# MCU.net
KiCad netlist of a schematic drawn in Altium Designer
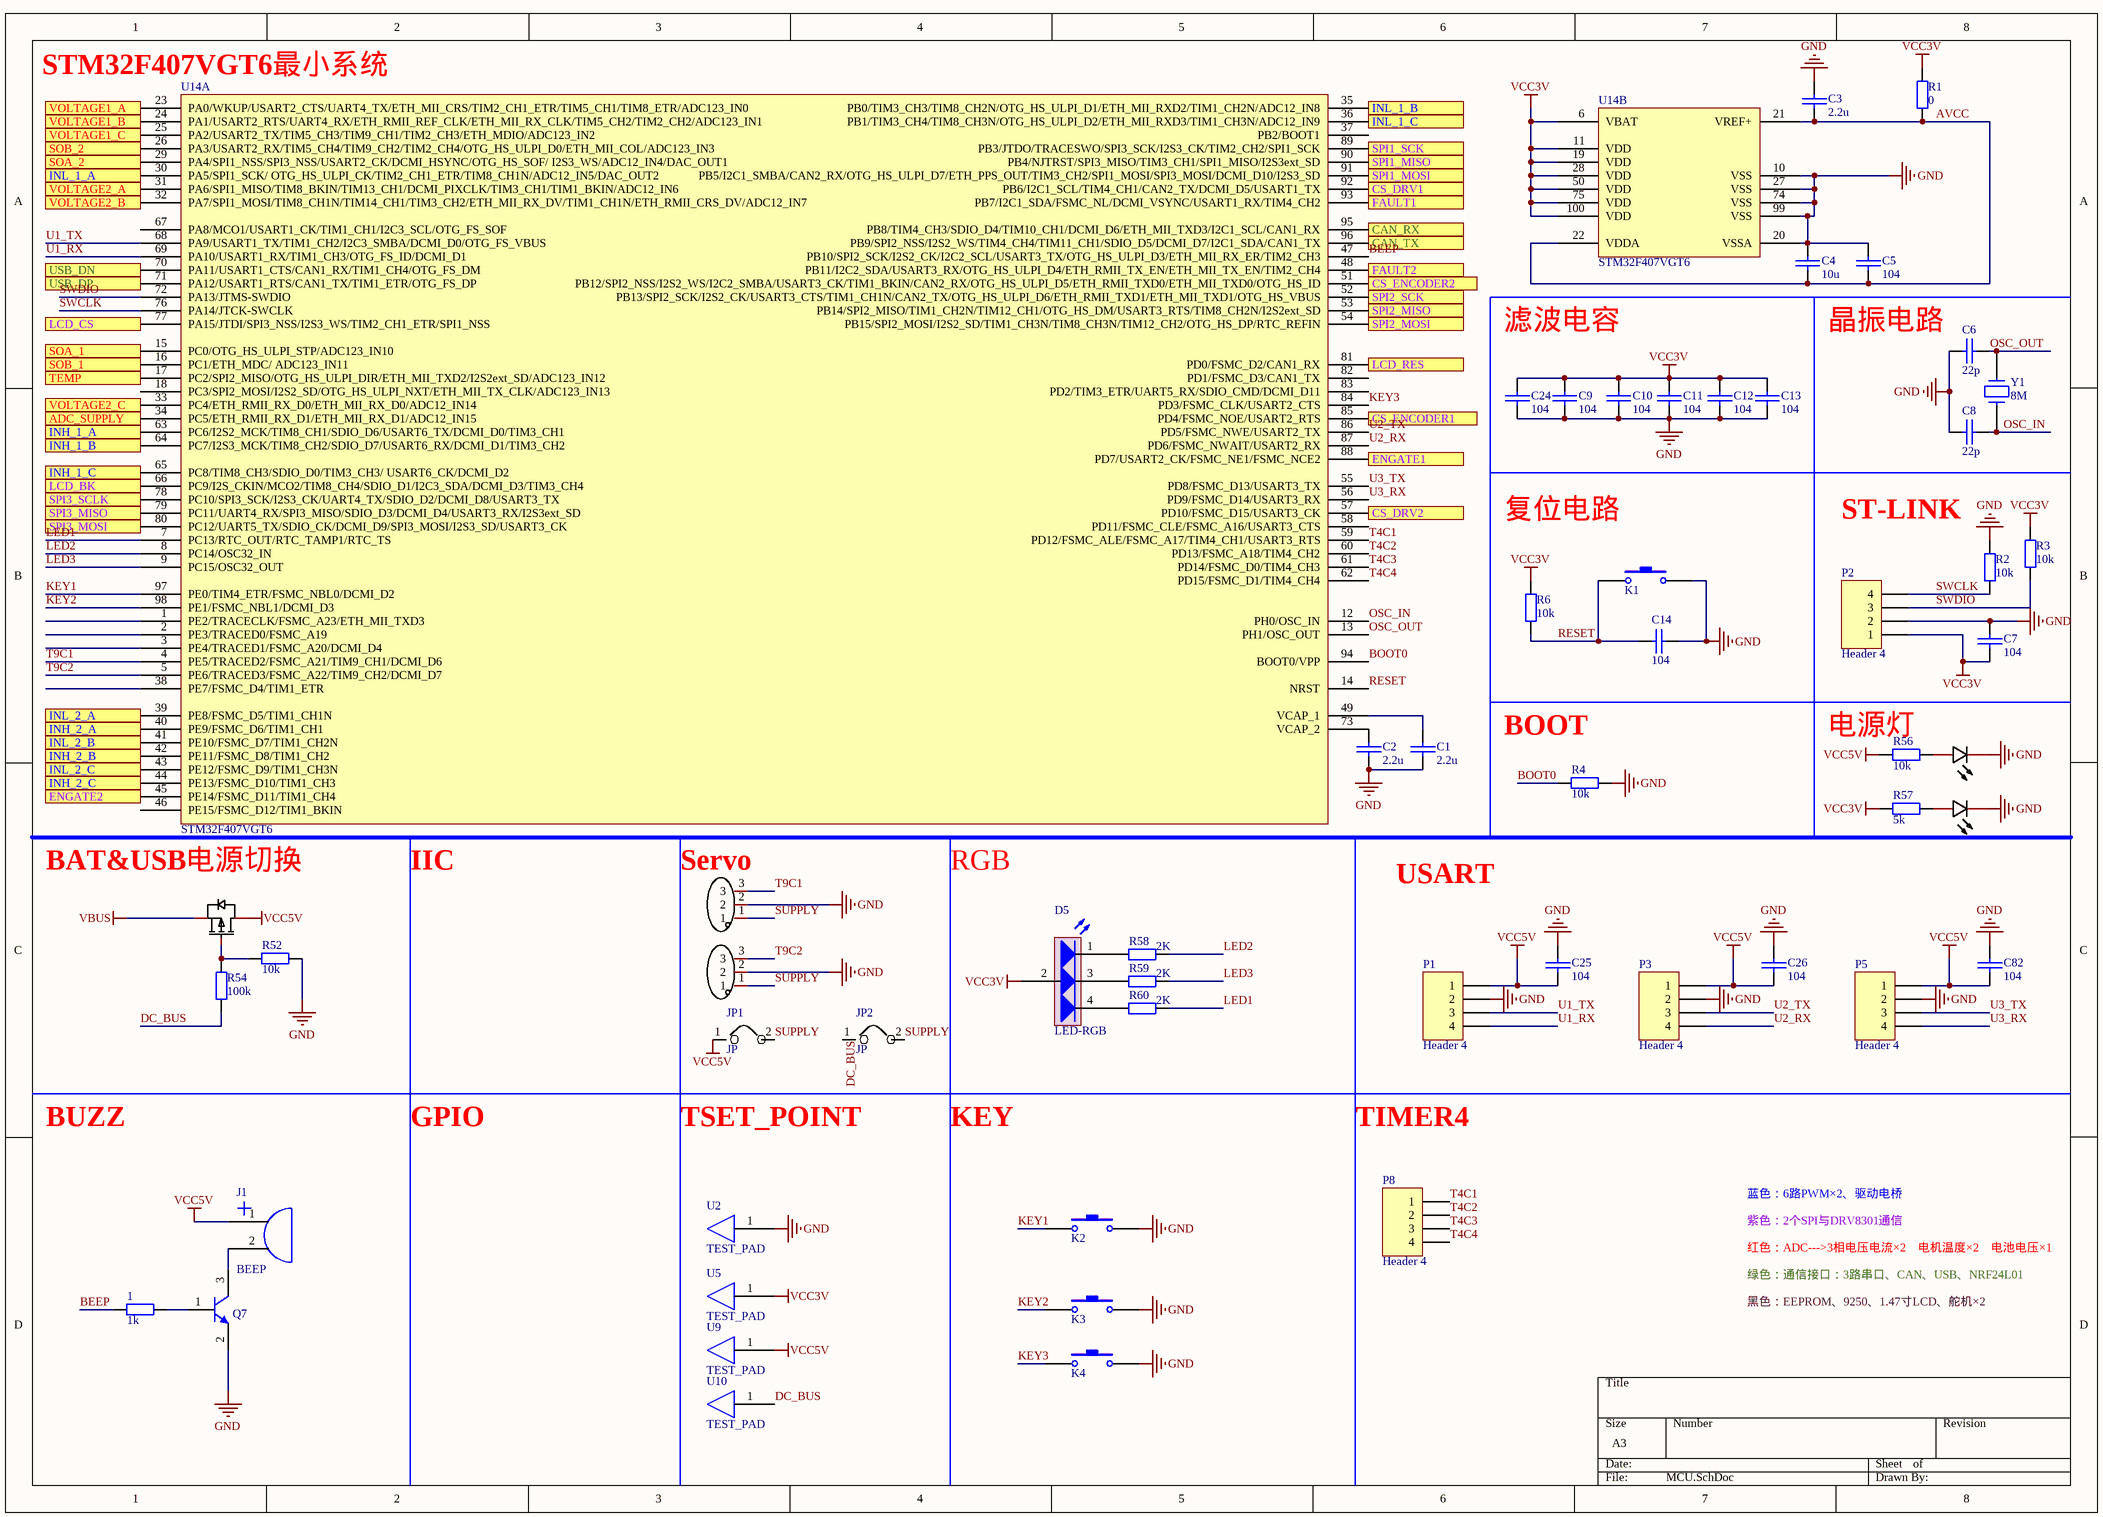
[diagram p0: MCU.SchDoc]

(export (version "E")
  (design (tool "Eeschema 10.0.6"))
  (components
    (comp (ref "1")
      (value "1k")
      (footprint "0402C")
      (description "Resistor")
      (fields (field (name "PUBLISHER") "Altium Limited"))
      (libsource (lib "") (part "Res2_1"))
    )
    (comp (ref "2")
      (value "NCD0603R1_C84263")
      (footprint "0603LED")
      (fields (field (name "MANUFACTURER") "国星光电") (field (name "MANUFACTURER PART") "NCD0603R1"))
      (libsource (lib "FOC") (part "0603LED"))
    )
    (comp (ref "3")
      (value "NCD0603R1_C84263")
      (footprint "0603LED")
      (fields (field (name "MANUFACTURER") "国星光电") (field (name "MANUFACTURER PART") "NCD0603R1"))
      (libsource (lib "FOC") (part "0603LED"))
    )
    (comp (ref "C1")
      (value "2.2u")
      (footprint "0402C")
      (fields (field (name "Comment") "CAP"))
      (libsource (lib "MY SCH LIB") (part "CAP"))
    )
    (comp (ref "C2")
      (value "2.2u")
      (footprint "0402C")
      (fields (field (name "Comment") "CAP"))
      (libsource (lib "MY SCH LIB") (part "CAP"))
    )
    (comp (ref "C3")
      (value "2.2u")
      (footprint "0402C")
      (fields (field (name "Comment") "CAP"))
      (libsource (lib "MY SCH LIB") (part "CAP"))
    )
    (comp (ref "C4")
      (value "10u")
      (footprint "0402C")
      (fields (field (name "Comment") "CAP"))
      (libsource (lib "MY SCH LIB") (part "CAP"))
    )
    (comp (ref "C5")
      (value "104")
      (footprint "0402C")
      (fields (field (name "Comment") "CAP"))
      (libsource (lib "MY SCH LIB") (part "CAP"))
    )
    (comp (ref "C6")
      (value "22p")
      (footprint "0402C")
      (fields (field (name "Comment") "CAP"))
      (libsource (lib "MY SCH LIB") (part "CAP"))
    )
    (comp (ref "C7")
      (value "104")
      (footprint "0402C")
      (fields (field (name "Comment") "CAP"))
      (libsource (lib "MY SCH LIB") (part "CAP"))
    )
    (comp (ref "C8")
      (value "22p")
      (footprint "0402C")
      (fields (field (name "Comment") "CAP"))
      (libsource (lib "MY SCH LIB") (part "CAP"))
    )
    (comp (ref "C9")
      (value "104")
      (footprint "0402C")
      (fields (field (name "Comment") "CAP"))
      (libsource (lib "MY SCH LIB") (part "CAP"))
    )
    (comp (ref "C10")
      (value "104")
      (footprint "0402C")
      (fields (field (name "Comment") "CAP"))
      (libsource (lib "MY SCH LIB") (part "CAP"))
    )
    (comp (ref "C11")
      (value "104")
      (footprint "0402C")
      (fields (field (name "Comment") "CAP"))
      (libsource (lib "MY SCH LIB") (part "CAP"))
    )
    (comp (ref "C12")
      (value "104")
      (footprint "0402C")
      (fields (field (name "Comment") "CAP"))
      (libsource (lib "MY SCH LIB") (part "CAP"))
    )
    (comp (ref "C13")
      (value "104")
      (footprint "0402C")
      (fields (field (name "Comment") "CAP"))
      (libsource (lib "MY SCH LIB") (part "CAP"))
    )
    (comp (ref "C14") (value "104") (footprint "0402C") (libsource (lib "平衡车") (part "CAP")))
    (comp (ref "C24")
      (value "104")
      (footprint "0402C")
      (fields (field (name "Comment") "CAP"))
      (libsource (lib "MY SCH LIB") (part "CAP"))
    )
    (comp (ref "C25")
      (value "104")
      (footprint "0402C")
      (description "Capacitor")
      (libsource (lib "Y常用") (part "Cap"))
    )
    (comp (ref "C26")
      (value "104")
      (footprint "0402C")
      (description "Capacitor")
      (libsource (lib "Y常用") (part "Cap"))
    )
    (comp (ref "C82")
      (value "104")
      (footprint "0402C")
      (description "Capacitor")
      (libsource (lib "Y常用") (part "Cap"))
    )
    (comp (ref "D5")
      (value "LED-RGB")
      (footprint "RGB")
      (description "三基色LED")
      (fields (field (name "PUBLISHER") "Altium Limited"))
      (libsource (lib "SMC_Devices") (part "LED-RGB"))
    )
    (comp (ref "J1")
      (value "BEEP")
      (footprint "无源蜂鸣器5020")
      (description "蜂鸣器")
      (libsource (lib "MY SCH LIB") (part "BEEP"))
    )
    (comp (ref "JP1") (value "JP") (footprint "跳线") (libsource (lib "FOC") (part "JP")))
    (comp (ref "JP2") (value "JP") (footprint "跳线") (libsource (lib "FOC") (part "JP")))
    (comp (ref "K1")
      (value "KEY")
      (footprint "KEY-SMD_L3.9-W3.0-P4.45")
      (libsource (lib "FOC") (part "KEY_1"))
    )
    (comp (ref "K2")
      (value "KEY")
      (footprint "KEY-SMD_L3.9-W3.0-P4.45")
      (libsource (lib "FOC") (part "KEY_1"))
    )
    (comp (ref "K3")
      (value "KEY")
      (footprint "KEY-SMD_L3.9-W3.0-P4.45")
      (libsource (lib "FOC") (part "KEY_1"))
    )
    (comp (ref "K4")
      (value "KEY")
      (footprint "KEY-SMD_L3.9-W3.0-P4.45")
      (libsource (lib "FOC") (part "KEY_1"))
    )
    (comp (ref "P1")
      (value "Header 4")
      (footprint "A1002WR-S-4P")
      (description "Header, 4-Pin")
      (fields (field (name "PUBLISHER") "Altium Limited"))
      (libsource (lib "FOC") (part "Header 4"))
    )
    (comp (ref "P2")
      (value "Header 4")
      (footprint "A1002WR-S-4P")
      (description "Header, 4-Pin")
      (fields (field (name "PUBLISHER") "Altium Limited"))
      (libsource (lib "MY SCH LIB__JCH") (part "Header 4"))
    )
    (comp (ref "P3")
      (value "Header 4")
      (footprint "A1002WR-S-4P")
      (description "Header, 4-Pin")
      (fields (field (name "PUBLISHER") "Altium Limited"))
      (libsource (lib "FOC") (part "Header 4"))
    )
    (comp (ref "P5")
      (value "Header 4")
      (footprint "A1002WR-S-4P")
      (description "Header, 4-Pin")
      (fields (field (name "PUBLISHER") "Altium Limited"))
      (libsource (lib "FOC") (part "Header 4"))
    )
    (comp (ref "P8")
      (value "Header 4")
      (footprint "A1002WR-S-4P")
      (description "Header, 4-Pin")
      (fields (field (name "PUBLISHER") "Altium Limited"))
      (libsource (lib "FOC") (part "Header 4"))
    )
    (comp (ref "Q7") (value "NPN") (footprint "SOT-23Q") (libsource (lib "MY SCH LIB__JCH") (part "NPN")))
    (comp (ref "Q15")
      (value "AO3401_C727156")
      (footprint "SOT-23Q")
      (fields (field (name "MANUFACTURER") "TWGMC(台湾迪嘉)") (field (name "MANUFACTURER PART") "AO3401"))
      (libsource (lib "FOC") (part "PMOS"))
    )
    (comp (ref "R1")
      (value "0")
      (footprint "0402R")
      (description "Resistor")
      (fields (field (name "PUBLISHER") "Altium Limited"))
      (libsource (lib "") (part "Res2_2"))
    )
    (comp (ref "R2")
      (value "10k")
      (footprint "0402R")
      (description "Resistor")
      (fields (field (name "PUBLISHER") "Altium Limited"))
      (libsource (lib "Miscellaneous Devices") (part "Res2"))
    )
    (comp (ref "R3")
      (value "10k")
      (footprint "0402R")
      (description "Resistor")
      (fields (field (name "PUBLISHER") "Altium Limited"))
      (libsource (lib "Miscellaneous Devices") (part "Res2"))
    )
    (comp (ref "R4")
      (value "10k")
      (footprint "0402R")
      (description "Resistor")
      (fields (field (name "PUBLISHER") "Altium Limited"))
      (libsource (lib "") (part "Res2_1"))
    )
    (comp (ref "R6")
      (value "10k")
      (footprint "0402R")
      (description "Resistor")
      (fields (field (name "PUBLISHER") "Altium Limited"))
      (libsource (lib "") (part "Res2_2"))
    )
    (comp (ref "R52")
      (value "10k")
      (footprint "0402R")
      (description "Resistor")
      (fields (field (name "PUBLISHER") "Altium Limited"))
      (libsource (lib "") (part "Res2_3"))
    )
    (comp (ref "R54")
      (value "100k")
      (footprint "0402R")
      (description "Resistor")
      (fields (field (name "PUBLISHER") "Altium Limited"))
      (libsource (lib "") (part "Res2_2"))
    )
    (comp (ref "R56")
      (value "10k")
      (footprint "0402R")
      (description "Resistor")
      (fields (field (name "PUBLISHER") "Altium Limited"))
      (libsource (lib "") (part "Res2_1"))
    )
    (comp (ref "R57")
      (value "5k")
      (footprint "0402R")
      (description "Resistor")
      (fields (field (name "PUBLISHER") "Altium Limited"))
      (libsource (lib "") (part "Res2_1"))
    )
    (comp (ref "R58")
      (value "2K")
      (footprint "0402R")
      (description "贴片电阻")
      (fields (field (name "Comment") "Res1") (field (name "PUBLISHER") "Altium Limited"))
      (libsource (lib "SMC_Devices") (part "Res1"))
    )
    (comp (ref "R59")
      (value "2K")
      (footprint "0402R")
      (description "贴片电阻")
      (fields (field (name "Comment") "Res1") (field (name "PUBLISHER") "Altium Limited"))
      (libsource (lib "SMC_Devices") (part "Res1"))
    )
    (comp (ref "R60")
      (value "2K")
      (footprint "0402R")
      (description "贴片电阻")
      (fields (field (name "Comment") "Res1") (field (name "PUBLISHER") "Altium Limited"))
      (libsource (lib "SMC_Devices") (part "Res1"))
    )
    (comp (ref "U2")
      (value "TEST_PAD")
      (footprint "TEST_PAD -SQUARE")
      (libsource (lib "FOC") (part "TEST_PAD"))
    )
    (comp (ref "U3")
      (value "MR30-M")
      (footprint "HDR2.54-LI-3P")
      (fields (field (name "MANUFACTURER") "AMASS(艾迈斯)"))
      (libsource (lib "FOC") (part "MR30-M"))
    )
    (comp (ref "U4")
      (value "MR30-M")
      (footprint "HDR2.54-LI-3P")
      (fields (field (name "MANUFACTURER") "AMASS(艾迈斯)"))
      (libsource (lib "FOC") (part "MR30-M"))
    )
    (comp (ref "U5")
      (value "TEST_PAD")
      (footprint "TEST_PAD -SQUARE")
      (libsource (lib "FOC") (part "TEST_PAD"))
    )
    (comp (ref "U9")
      (value "TEST_PAD")
      (footprint "TEST_PAD -SQUARE")
      (libsource (lib "FOC") (part "TEST_PAD"))
    )
    (comp (ref "U10")
      (value "TEST_PAD")
      (footprint "TEST_PAD -SQUARE")
      (libsource (lib "FOC") (part "TEST_PAD"))
    )
    (comp (ref "U14")
      (value "STM32F407VGT6")
      (footprint "LQFP-100_L14.0-W14.0-P0.50-LS16.0-BL")
      (libsource (lib "FOC") (part "STM32F407VGT6"))
    )
    (comp (ref "Y1")
      (value "8M")
      (footprint "晶振")
      (description "Crystal")
      (libsource (lib "MY SCH LIB") (part "CRYSTAL"))
    )
  )
  (nets
    (net (code "1") (name "/ADC_SUPPLY") (class "Default")
      (node (ref "U14") (pin "34") (pinfunction "PC5/ETH_RMII_RX_D1/ETH_MII_RX_D1/ADC12_IN15_34") (pintype "passive"))
    )
    (net (code "2") (name "/AVCC") (class "Default")
      (node (ref "C3") (pin "1") (pinfunction "1_1") (pintype "passive"))
      (node (ref "C4") (pin "2") (pinfunction "2_2") (pintype "passive"))
      (node (ref "C5") (pin "2") (pinfunction "2_2") (pintype "passive"))
      (node (ref "R1") (pin "2") (pinfunction "2_2") (pintype "passive"))
      (node (ref "U14") (pin "21") (pinfunction "VREF+_21") (pintype "passive"))
      (node (ref "U14") (pin "22") (pinfunction "VDDA_22") (pintype "passive"))
    )
    (net (code "3") (name "/BEEP") (class "Default")
      (node (ref "1") (pin "1") (pinfunction "1_1") (pintype "passive"))
      (node (ref "U14") (pin "47") (pinfunction "PB10/SPI2_SCK/I2S2_CK/I2C2_SCL/USART3_TX/OTG_HS_ULPI_D3/ETH_MII_RX_ER/TIM2_CH3_47") (pintype "passive"))
    )
    (net (code "4") (name "/BOOT0") (class "Default")
      (node (ref "R4") (pin "1") (pinfunction "1_1") (pintype "passive"))
      (node (ref "U14") (pin "94") (pinfunction "BOOT0/VPP_94") (pintype "passive"))
    )
    (net (code "5") (name "/CAN_RX") (class "Default")
      (node (ref "U14") (pin "95") (pinfunction "PB8/TIM4_CH3/SDIO_D4/TIM10_CH1/DCMI_D6/ETH_MII_TXD3/I2C1_SCL/CAN1_RX_95") (pintype "passive"))
    )
    (net (code "6") (name "/CAN_TX") (class "Default")
      (node (ref "U14") (pin "96") (pinfunction "PB9/SPI2_NSS/I2S2_WS/TIM4_CH4/TIM11_CH1/SDIO_D5/DCMI_D7/I2C1_SDA/CAN1_TX_96") (pintype "passive"))
    )
    (net (code "7") (name "/CS_DRV1") (class "Default")
      (node (ref "U14") (pin "92") (pinfunction "PB6/I2C1_SCL/TIM4_CH1/CAN2_TX/DCMI_D5/USART1_TX_92") (pintype "passive"))
    )
    (net (code "8") (name "/CS_DRV2") (class "Default")
      (node (ref "U14") (pin "57") (pinfunction "PD10/FSMC_D15/USART3_CK_57") (pintype "passive"))
    )
    (net (code "9") (name "/CS_ENCODER1") (class "Default")
      (node (ref "U14") (pin "85") (pinfunction "PD4/FSMC_NOE/USART2_RTS_85") (pintype "passive"))
    )
    (net (code "10") (name "/CS_ENCODER2") (class "Default")
      (node (ref "U14") (pin "51") (pinfunction "PB12/SPI2_NSS/I2S2_WS/I2C2_SMBA/USART3_CK/TIM1_BKIN/CAN2_RX/OTG_HS_ULPI_D5/ETH_RMII_TXD0/ETH_MII_TXD0/OTG_HS_ID_51") (pintype "passive"))
    )
    (net (code "11") (name "/DC_BUS") (class "Default")
      (node (ref "JP2") (pin "1") (pinfunction "1_1") (pintype "passive"))
      (node (ref "R54") (pin "2") (pinfunction "2_2") (pintype "passive"))
      (node (ref "U10") (pin "1") (pinfunction "2_1") (pintype "passive"))
    )
    (net (code "12") (name "/ENGATE1") (class "Default")
      (node (ref "U14") (pin "88") (pinfunction "PD7/USART2_CK/FSMC_NE1/FSMC_NCE2_88") (pintype "passive"))
    )
    (net (code "13") (name "/ENGATE2") (class "Default")
      (node (ref "U14") (pin "45") (pinfunction "PE14/FSMC_D11/TIM1_CH4_45") (pintype "passive"))
    )
    (net (code "14") (name "/FAULT1") (class "Default")
      (node (ref "U14") (pin "93") (pinfunction "PB7/I2C1_SDA/FSMC_NL/DCMI_VSYNC/USART1_RX/TIM4_CH2_93") (pintype "passive"))
    )
    (net (code "15") (name "/FAULT2") (class "Default")
      (node (ref "U14") (pin "48") (pinfunction "PB11/I2C2_SDA/USART3_RX/OTG_HS_ULPI_D4/ETH_RMII_TX_EN/ETH_MII_TX_EN/TIM2_CH4_48") (pintype "passive"))
    )
    (net (code "16") (name "/INH_1_A") (class "Default")
      (node (ref "U14") (pin "63") (pinfunction "PC6/I2S2_MCK/TIM8_CH1/SDIO_D6/USART6_TX/DCMI_D0/TIM3_CH1_63") (pintype "passive"))
    )
    (net (code "17") (name "/INH_1_B") (class "Default")
      (node (ref "U14") (pin "64") (pinfunction "PC7/I2S3_MCK/TIM8_CH2/SDIO_D7/USART6_RX/DCMI_D1/TIM3_CH2_64") (pintype "passive"))
    )
    (net (code "18") (name "/INH_1_C") (class "Default")
      (node (ref "U14") (pin "65") (pinfunction "PC8/TIM8_CH3/SDIO_D0/TIM3_CH3/_USART6_CK/DCMI_D2_65") (pintype "passive"))
    )
    (net (code "19") (name "/INH_2_A") (class "Default")
      (node (ref "U14") (pin "40") (pinfunction "PE9/FSMC_D6/TIM1_CH1_40") (pintype "passive"))
    )
    (net (code "20") (name "/INH_2_B") (class "Default")
      (node (ref "U14") (pin "42") (pinfunction "PE11/FSMC_D8/TIM1_CH2_42") (pintype "passive"))
    )
    (net (code "21") (name "/INH_2_C") (class "Default")
      (node (ref "U14") (pin "44") (pinfunction "PE13/FSMC_D10/TIM1_CH3_44") (pintype "passive"))
    )
    (net (code "22") (name "/INL_1_A") (class "Default")
      (node (ref "U14") (pin "30") (pinfunction "PA5/SPI1_SCK/_OTG_HS_ULPI_CK/TIM2_CH1_ETR/TIM8_CH1N/ADC12_IN5/DAC_OUT2_30") (pintype "passive"))
    )
    (net (code "23") (name "/INL_1_B") (class "Default")
      (node (ref "U14") (pin "35") (pinfunction "PB0/TIM3_CH3/TIM8_CH2N/OTG_HS_ULPI_D1/ETH_MII_RXD2/TIM1_CH2N/ADC12_IN8_35") (pintype "passive"))
    )
    (net (code "24") (name "/INL_1_C") (class "Default")
      (node (ref "U14") (pin "36") (pinfunction "PB1/TIM3_CH4/TIM8_CH3N/OTG_HS_ULPI_D2/ETH_MII_RXD3/TIM1_CH3N/ADC12_IN9_36") (pintype "passive"))
    )
    (net (code "25") (name "/INL_2_A") (class "Default")
      (node (ref "U14") (pin "39") (pinfunction "PE8/FSMC_D5/TIM1_CH1N_39") (pintype "passive"))
    )
    (net (code "26") (name "/INL_2_B") (class "Default")
      (node (ref "U14") (pin "41") (pinfunction "PE10/FSMC_D7/TIM1_CH2N_41") (pintype "passive"))
    )
    (net (code "27") (name "/INL_2_C") (class "Default")
      (node (ref "U14") (pin "43") (pinfunction "PE12/FSMC_D9/TIM1_CH3N_43") (pintype "passive"))
    )
    (net (code "28") (name "/KEY1") (class "Default")
      (node (ref "K2") (pin "1") (pinfunction "1_1") (pintype "passive"))
      (node (ref "U14") (pin "97") (pinfunction "PE0/TIM4_ETR/FSMC_NBL0/DCMI_D2_97") (pintype "passive"))
    )
    (net (code "29") (name "/KEY2") (class "Default")
      (node (ref "K3") (pin "1") (pinfunction "1_1") (pintype "passive"))
      (node (ref "U14") (pin "98") (pinfunction "PE1/FSMC_NBL1/DCMI_D3_98") (pintype "passive"))
    )
    (net (code "30") (name "/KEY3") (class "Default")
      (node (ref "K4") (pin "1") (pinfunction "1_1") (pintype "passive"))
      (node (ref "U14") (pin "84") (pinfunction "PD3/FSMC_CLK/USART2_CTS_84") (pintype "passive"))
    )
    (net (code "31") (name "/LCD_BK") (class "Default")
      (node (ref "U14") (pin "66") (pinfunction "PC9/I2S_CKIN/MCO2/TIM8_CH4/SDIO_D1/I2C3_SDA/DCMI_D3/TIM3_CH4_66") (pintype "passive"))
    )
    (net (code "32") (name "/LCD_CS") (class "Default")
      (node (ref "U14") (pin "77") (pinfunction "PA15/JTDI/SPI3_NSS/I2S3_WS/TIM2_CH1_ETR/SPI1_NSS_77") (pintype "passive"))
    )
    (net (code "33") (name "/LCD_RES") (class "Default")
      (node (ref "U14") (pin "81") (pinfunction "PD0/FSMC_D2/CAN1_RX_81") (pintype "passive"))
    )
    (net (code "34") (name "/LED1") (class "Default")
      (node (ref "R60") (pin "2") (pinfunction "2_2") (pintype "passive"))
      (node (ref "U14") (pin "7") (pinfunction "PC13/RTC_OUT/RTC_TAMP1/RTC_TS_7") (pintype "passive"))
    )
    (net (code "35") (name "/LED2") (class "Default")
      (node (ref "R58") (pin "2") (pinfunction "2_2") (pintype "passive"))
      (node (ref "U14") (pin "8") (pinfunction "PC14/OSC32_IN_8") (pintype "passive"))
    )
    (net (code "36") (name "/LED3") (class "Default")
      (node (ref "R59") (pin "2") (pinfunction "2_2") (pintype "passive"))
      (node (ref "U14") (pin "9") (pinfunction "PC15/OSC32_OUT_9") (pintype "passive"))
    )
    (net (code "37") (name "/OSC_IN") (class "Default")
      (node (ref "C8") (pin "1") (pinfunction "1_1") (pintype "passive"))
      (node (ref "U14") (pin "12") (pinfunction "PH0/OSC_IN_12") (pintype "passive"))
      (node (ref "Y1") (pin "2") (pinfunction "2_2") (pintype "passive"))
    )
    (net (code "38") (name "/OSC_OUT") (class "Default")
      (node (ref "C6") (pin "1") (pinfunction "1_1") (pintype "passive"))
      (node (ref "U14") (pin "13") (pinfunction "PH1/OSC_OUT_13") (pintype "passive"))
      (node (ref "Y1") (pin "1") (pinfunction "1_1") (pintype "passive"))
    )
    (net (code "39") (name "/RESET") (class "Default")
      (node (ref "C14") (pin "1") (pinfunction "1_1") (pintype "passive"))
      (node (ref "K1") (pin "1") (pinfunction "1_1") (pintype "passive"))
      (node (ref "R6") (pin "2") (pinfunction "2_2") (pintype "passive"))
      (node (ref "U14") (pin "14") (pinfunction "NRST_14") (pintype "passive"))
    )
    (net (code "40") (name "/SOA_1") (class "Default")
      (node (ref "U14") (pin "15") (pinfunction "PC0/OTG_HS_ULPI_STP/ADC123_IN10_15") (pintype "passive"))
    )
    (net (code "41") (name "/SOA_2") (class "Default")
      (node (ref "U14") (pin "29") (pinfunction "PA4/SPI1_NSS/SPI3_NSS/USART2_CK/DCMI_HSYNC/OTG_HS_SOF/_I2S3_WS/ADC12_IN4/DAC_OUT1_29") (pintype "passive"))
    )
    (net (code "42") (name "/SOB_1") (class "Default")
      (node (ref "U14") (pin "16") (pinfunction "PC1/ETH_MDC/_ADC123_IN11_16") (pintype "passive"))
    )
    (net (code "43") (name "/SOB_2") (class "Default")
      (node (ref "U14") (pin "26") (pinfunction "PA3/USART2_RX/TIM5_CH4/TIM9_CH2/TIM2_CH4/OTG_HS_ULPI_D0/ETH_MII_COL/ADC123_IN3_26") (pintype "passive"))
    )
    (net (code "44") (name "/SPI1_MISO") (class "Default")
      (node (ref "U14") (pin "90") (pinfunction "PB4/NJTRST/SPI3_MISO/TIM3_CH1/SPI1_MISO/I2S3ext_SD_90") (pintype "passive"))
    )
    (net (code "45") (name "/SPI1_MOSI") (class "Default")
      (node (ref "U14") (pin "91") (pinfunction "PB5/I2C1_SMBA/CAN2_RX/OTG_HS_ULPI_D7/ETH_PPS_OUT/TIM3_CH2/SPI1_MOSI/SPI3_MOSI/DCMI_D10/I2S3_SD_91") (pintype "passive"))
    )
    (net (code "46") (name "/SPI1_SCK") (class "Default")
      (node (ref "U14") (pin "89") (pinfunction "PB3/JTDO/TRACESWO/SPI3_SCK/I2S3_CK/TIM2_CH2/SPI1_SCK_89") (pintype "passive"))
    )
    (net (code "47") (name "/SPI2_MISO") (class "Default")
      (node (ref "U14") (pin "53") (pinfunction "PB14/SPI2_MISO/TIM1_CH2N/TIM12_CH1/OTG_HS_DM/USART3_RTS/TIM8_CH2N/I2S2ext_SD_53") (pintype "passive"))
    )
    (net (code "48") (name "/SPI2_MOSI") (class "Default")
      (node (ref "U14") (pin "54") (pinfunction "PB15/SPI2_MOSI/I2S2_SD/TIM1_CH3N/TIM8_CH3N/TIM12_CH2/OTG_HS_DP/RTC_REFIN_54") (pintype "passive"))
    )
    (net (code "49") (name "/SPI2_SCK") (class "Default")
      (node (ref "U14") (pin "52") (pinfunction "PB13/SPI2_SCK/I2S2_CK/USART3_CTS/TIM1_CH1N/CAN2_TX/OTG_HS_ULPI_D6/ETH_RMII_TXD1/ETH_MII_TXD1/OTG_HS_VBUS_52") (pintype "passive"))
    )
    (net (code "50") (name "/SPI3_MISO") (class "Default")
      (node (ref "U14") (pin "79") (pinfunction "PC11/UART4_RX/SPI3_MISO/SDIO_D3/DCMI_D4/USART3_RX/I2S3ext_SD_79") (pintype "passive"))
    )
    (net (code "51") (name "/SPI3_MOSI") (class "Default")
      (node (ref "U14") (pin "80") (pinfunction "PC12/UART5_TX/SDIO_CK/DCMI_D9/SPI3_MOSI/I2S3_SD/USART3_CK_80") (pintype "passive"))
    )
    (net (code "52") (name "/SPI3_SCLK") (class "Default")
      (node (ref "U14") (pin "78") (pinfunction "PC10/SPI3_SCK/I2S3_CK/UART4_TX/SDIO_D2/DCMI_D8/USART3_TX_78") (pintype "passive"))
    )
    (net (code "53") (name "/SUPPLY") (class "Default")
      (node (ref "JP1") (pin "2") (pinfunction "2_2") (pintype "passive"))
      (node (ref "JP2") (pin "2") (pinfunction "2_2") (pintype "passive"))
      (node (ref "U3") (pin "1") (pinfunction "1_1") (pintype "passive"))
      (node (ref "U4") (pin "1") (pinfunction "1_1") (pintype "passive"))
    )
    (net (code "54") (name "/SWCLK") (class "Default")
      (node (ref "P2") (pin "4") (pinfunction "4_4") (pintype "passive"))
      (node (ref "R2") (pin "1") (pinfunction "1_1") (pintype "passive"))
      (node (ref "U14") (pin "76") (pinfunction "PA14/JTCK-SWCLK_76") (pintype "passive"))
    )
    (net (code "55") (name "/SWDIO") (class "Default")
      (node (ref "P2") (pin "3") (pinfunction "3_3") (pintype "passive"))
      (node (ref "R3") (pin "1") (pinfunction "1_1") (pintype "passive"))
      (node (ref "U14") (pin "72") (pinfunction "PA13/JTMS-SWDIO_72") (pintype "passive"))
    )
    (net (code "56") (name "/T4C1") (class "Default")
      (node (ref "P8") (pin "1") (pinfunction "1_1") (pintype "passive"))
      (node (ref "U14") (pin "59") (pinfunction "PD12/FSMC_ALE/FSMC_A17/TIM4_CH1/USART3_RTS_59") (pintype "passive"))
    )
    (net (code "57") (name "/T4C2") (class "Default")
      (node (ref "P8") (pin "2") (pinfunction "2_2") (pintype "passive"))
      (node (ref "U14") (pin "60") (pinfunction "PD13/FSMC_A18/TIM4_CH2_60") (pintype "passive"))
    )
    (net (code "58") (name "/T4C3") (class "Default")
      (node (ref "P8") (pin "3") (pinfunction "3_3") (pintype "passive"))
      (node (ref "U14") (pin "61") (pinfunction "PD14/FSMC_D0/TIM4_CH3_61") (pintype "passive"))
    )
    (net (code "59") (name "/T4C4") (class "Default")
      (node (ref "P8") (pin "4") (pinfunction "4_4") (pintype "passive"))
      (node (ref "U14") (pin "62") (pinfunction "PD15/FSMC_D1/TIM4_CH4_62") (pintype "passive"))
    )
    (net (code "60") (name "/T9C1") (class "Default")
      (node (ref "U14") (pin "4") (pinfunction "PE5/TRACED2/FSMC_A21/TIM9_CH1/DCMI_D6_4") (pintype "passive"))
      (node (ref "U3") (pin "3") (pinfunction "3_3") (pintype "passive"))
    )
    (net (code "61") (name "/T9C2") (class "Default")
      (node (ref "U14") (pin "5") (pinfunction "PE6/TRACED3/FSMC_A22/TIM9_CH2/DCMI_D7_5") (pintype "passive"))
      (node (ref "U4") (pin "3") (pinfunction "3_3") (pintype "passive"))
    )
    (net (code "62") (name "/TEMP") (class "Default")
      (node (ref "U14") (pin "17") (pinfunction "PC2/SPI2_MISO/OTG_HS_ULPI_DIR/ETH_MII_TXD2/I2S2ext_SD/ADC123_IN12_17") (pintype "passive"))
    )
    (net (code "63") (name "/U1_RX") (class "Default")
      (node (ref "P1") (pin "4") (pinfunction "4_4") (pintype "passive"))
      (node (ref "U14") (pin "69") (pinfunction "PA10/USART1_RX/TIM1_CH3/OTG_FS_ID/DCMI_D1_69") (pintype "passive"))
    )
    (net (code "64") (name "/U1_TX") (class "Default")
      (node (ref "P1") (pin "3") (pinfunction "3_3") (pintype "passive"))
      (node (ref "U14") (pin "68") (pinfunction "PA9/USART1_TX/TIM1_CH2/I2C3_SMBA/DCMI_D0/OTG_FS_VBUS_68") (pintype "passive"))
    )
    (net (code "65") (name "/U2_RX") (class "Default")
      (node (ref "P3") (pin "4") (pinfunction "4_4") (pintype "passive"))
      (node (ref "U14") (pin "87") (pinfunction "PD6/FSMC_NWAIT/USART2_RX_87") (pintype "passive"))
    )
    (net (code "66") (name "/U2_TX") (class "Default")
      (node (ref "P3") (pin "3") (pinfunction "3_3") (pintype "passive"))
      (node (ref "U14") (pin "86") (pinfunction "PD5/FSMC_NWE/USART2_TX_86") (pintype "passive"))
    )
    (net (code "67") (name "/U3_RX") (class "Default")
      (node (ref "P5") (pin "4") (pinfunction "4_4") (pintype "passive"))
      (node (ref "U14") (pin "56") (pinfunction "PD9/FSMC_D14/USART3_RX_56") (pintype "passive"))
    )
    (net (code "68") (name "/U3_TX") (class "Default")
      (node (ref "P5") (pin "3") (pinfunction "3_3") (pintype "passive"))
      (node (ref "U14") (pin "55") (pinfunction "PD8/FSMC_D13/USART3_TX_55") (pintype "passive"))
    )
    (net (code "69") (name "/USB_DN") (class "Default")
      (node (ref "U14") (pin "70") (pinfunction "PA11/USART1_CTS/CAN1_RX/TIM1_CH4/OTG_FS_DM_70") (pintype "passive"))
    )
    (net (code "70") (name "/USB_DP") (class "Default")
      (node (ref "U14") (pin "71") (pinfunction "PA12/USART1_RTS/CAN1_TX/TIM1_ETR/OTG_FS_DP_71") (pintype "passive"))
    )
    (net (code "71") (name "/VOLTAGE1_A") (class "Default")
      (node (ref "U14") (pin "23") (pinfunction "PA0/WKUP/USART2_CTS/UART4_TX/ETH_MII_CRS/TIM2_CH1_ETR/TIM5_CH1/TIM8_ETR/ADC123_IN0_23") (pintype "passive"))
    )
    (net (code "72") (name "/VOLTAGE1_B") (class "Default")
      (node (ref "U14") (pin "24") (pinfunction "PA1/USART2_RTS/UART4_RX/ETH_RMII_REF_CLK/ETH_MII_RX_CLK/TIM5_CH2/TIM2_CH2/ADC123_IN1_24") (pintype "passive"))
    )
    (net (code "73") (name "/VOLTAGE1_C") (class "Default")
      (node (ref "U14") (pin "25") (pinfunction "PA2/USART2_TX/TIM5_CH3/TIM9_CH1/TIM2_CH3/ETH_MDIO/ADC123_IN2_25") (pintype "passive"))
    )
    (net (code "74") (name "/VOLTAGE2_A") (class "Default")
      (node (ref "U14") (pin "31") (pinfunction "PA6/SPI1_MISO/TIM8_BKIN/TIM13_CH1/DCMI_PIXCLK/TIM3_CH1/TIM1_BKIN/ADC12_IN6_31") (pintype "passive"))
    )
    (net (code "75") (name "/VOLTAGE2_B") (class "Default")
      (node (ref "U14") (pin "32") (pinfunction "PA7/SPI1_MOSI/TIM8_CH1N/TIM14_CH1/TIM3_CH2/ETH_MII_RX_DV/TIM1_CH1N/ETH_RMII_CRS_DV/ADC12_IN7_32") (pintype "passive"))
    )
    (net (code "76") (name "/VOLTAGE2_C") (class "Default")
      (node (ref "U14") (pin "33") (pinfunction "PC4/ETH_RMII_RX_D0/ETH_MII_RX_D0/ADC12_IN14_33") (pintype "passive"))
    )
    (net (code "77") (name "GND") (class "Default")
      (node (ref "2") (pin "1") (pinfunction "K_1") (pintype "passive"))
      (node (ref "3") (pin "1") (pinfunction "K_1") (pintype "passive"))
      (node (ref "C1") (pin "1") (pinfunction "1_1") (pintype "passive"))
      (node (ref "C10") (pin "2") (pinfunction "2_2") (pintype "passive"))
      (node (ref "C11") (pin "2") (pinfunction "2_2") (pintype "passive"))
      (node (ref "C12") (pin "2") (pinfunction "2_2") (pintype "passive"))
      (node (ref "C13") (pin "2") (pinfunction "2_2") (pintype "passive"))
      (node (ref "C14") (pin "2") (pinfunction "2_2") (pintype "passive"))
      (node (ref "C2") (pin "1") (pinfunction "1_1") (pintype "passive"))
      (node (ref "C24") (pin "2") (pinfunction "2_2") (pintype "passive"))
      (node (ref "C25") (pin "2") (pintype "passive"))
      (node (ref "C26") (pin "2") (pintype "passive"))
      (node (ref "C3") (pin "2") (pinfunction "2_2") (pintype "passive"))
      (node (ref "C4") (pin "1") (pinfunction "1_1") (pintype "passive"))
      (node (ref "C5") (pin "1") (pinfunction "1_1") (pintype "passive"))
      (node (ref "C6") (pin "2") (pinfunction "2_2") (pintype "passive"))
      (node (ref "C7") (pin "1") (pinfunction "1_1") (pintype "passive"))
      (node (ref "C8") (pin "2") (pinfunction "2_2") (pintype "passive"))
      (node (ref "C82") (pin "2") (pintype "passive"))
      (node (ref "C9") (pin "2") (pinfunction "2_2") (pintype "passive"))
      (node (ref "K1") (pin "2") (pinfunction "2_2") (pintype "passive"))
      (node (ref "K2") (pin "2") (pinfunction "2_2") (pintype "passive"))
      (node (ref "K3") (pin "2") (pinfunction "2_2") (pintype "passive"))
      (node (ref "K4") (pin "2") (pinfunction "2_2") (pintype "passive"))
      (node (ref "P1") (pin "2") (pinfunction "2_2") (pintype "passive"))
      (node (ref "P2") (pin "2") (pinfunction "2_2") (pintype "passive"))
      (node (ref "P3") (pin "2") (pinfunction "2_2") (pintype "passive"))
      (node (ref "P5") (pin "2") (pinfunction "2_2") (pintype "passive"))
      (node (ref "Q7") (pin "2") (pinfunction "E_2") (pintype "passive"))
      (node (ref "R2") (pin "2") (pinfunction "2_2") (pintype "passive"))
      (node (ref "R4") (pin "2") (pinfunction "2_2") (pintype "passive"))
      (node (ref "R52") (pin "1") (pinfunction "1_1") (pintype "passive"))
      (node (ref "U14") (pin "10") (pinfunction "VSS_10") (pintype "passive"))
      (node (ref "U14") (pin "20") (pinfunction "VSSA_20") (pintype "passive"))
      (node (ref "U14") (pin "27") (pinfunction "VSS_27") (pintype "passive"))
      (node (ref "U14") (pin "74") (pinfunction "VSS_74") (pintype "passive"))
      (node (ref "U14") (pin "99") (pinfunction "VSS_99") (pintype "passive"))
      (node (ref "U2") (pin "1") (pinfunction "2_1") (pintype "passive"))
      (node (ref "U3") (pin "2") (pinfunction "2_2") (pintype "passive"))
      (node (ref "U4") (pin "2") (pinfunction "2_2") (pintype "passive"))
    )
    (net (code "78") (name "Net-(2-A)") (class "Default")
      (node (ref "2") (pin "2") (pinfunction "A_2") (pintype "passive"))
      (node (ref "R56") (pin "2") (pinfunction "2_2") (pintype "passive"))
    )
    (net (code "79") (name "Net-(3-A)") (class "Default")
      (node (ref "3") (pin "2") (pinfunction "A_2") (pintype "passive"))
      (node (ref "R57") (pin "2") (pinfunction "2_2") (pintype "passive"))
    )
    (net (code "80") (name "Net-(D5-B)") (class "Default")
      (node (ref "D5") (pin "4") (pinfunction "B_4") (pintype "passive"))
      (node (ref "R60") (pin "1") (pinfunction "1_1") (pintype "passive"))
    )
    (net (code "81") (name "Net-(D5-G)") (class "Default")
      (node (ref "D5") (pin "3") (pinfunction "G_3") (pintype "passive"))
      (node (ref "R59") (pin "1") (pinfunction "1_1") (pintype "passive"))
    )
    (net (code "82") (name "Net-(D5-R)") (class "Default")
      (node (ref "D5") (pin "1") (pinfunction "R_1") (pintype "passive"))
      (node (ref "R58") (pin "1") (pinfunction "1_1") (pintype "passive"))
    )
    (net (code "83") (name "Net-(J1-1)") (class "Default")
      (node (ref "J1") (pin "2") (pinfunction "1_2") (pintype "passive"))
      (node (ref "Q7") (pin "3") (pinfunction "C_3") (pintype "passive"))
    )
    (net (code "84") (name "Net-(Q7-B)") (class "Default")
      (node (ref "1") (pin "2") (pinfunction "2_2") (pintype "passive"))
      (node (ref "Q7") (pin "1") (pinfunction "B_1") (pintype "passive"))
    )
    (net (code "85") (name "Net-(Q15-G)") (class "Default")
      (node (ref "Q15") (pin "1") (pinfunction "G_1") (pintype "passive"))
      (node (ref "R52") (pin "2") (pinfunction "2_2") (pintype "passive"))
      (node (ref "R54") (pin "1") (pinfunction "1_1") (pintype "passive"))
    )
    (net (code "86") (name "Net-(U14A-VCAP_1)") (class "Default")
      (node (ref "C1") (pin "2") (pinfunction "2_2") (pintype "passive"))
      (node (ref "U14") (pin "49") (pinfunction "VCAP_1_49") (pintype "passive"))
    )
    (net (code "87") (name "Net-(U14A-VCAP_2)") (class "Default")
      (node (ref "C2") (pin "2") (pinfunction "2_2") (pintype "passive"))
      (node (ref "U14") (pin "73") (pinfunction "VCAP_2_73") (pintype "passive"))
    )
    (net (code "88") (name "VBUS") (class "Default")
      (node (ref "Q15") (pin "2") (pinfunction "S_2") (pintype "passive"))
    )
    (net (code "89") (name "VCC3V") (class "Default")
      (node (ref "C10") (pin "1") (pinfunction "1_1") (pintype "passive"))
      (node (ref "C11") (pin "1") (pinfunction "1_1") (pintype "passive"))
      (node (ref "C12") (pin "1") (pinfunction "1_1") (pintype "passive"))
      (node (ref "C13") (pin "1") (pinfunction "1_1") (pintype "passive"))
      (node (ref "C24") (pin "1") (pinfunction "1_1") (pintype "passive"))
      (node (ref "C7") (pin "2") (pinfunction "2_2") (pintype "passive"))
      (node (ref "C9") (pin "1") (pinfunction "1_1") (pintype "passive"))
      (node (ref "D5") (pin "2") (pinfunction "A_2") (pintype "passive"))
      (node (ref "P2") (pin "1") (pinfunction "1_1") (pintype "passive"))
      (node (ref "R1") (pin "1") (pinfunction "1_1") (pintype "passive"))
      (node (ref "R3") (pin "2") (pinfunction "2_2") (pintype "passive"))
      (node (ref "R57") (pin "1") (pinfunction "1_1") (pintype "passive"))
      (node (ref "R6") (pin "1") (pinfunction "1_1") (pintype "passive"))
      (node (ref "U14") (pin "100") (pinfunction "VDD_100") (pintype "passive"))
      (node (ref "U14") (pin "11") (pinfunction "VDD_11") (pintype "passive"))
      (node (ref "U14") (pin "19") (pinfunction "VDD_19") (pintype "passive"))
      (node (ref "U14") (pin "28") (pinfunction "VDD_28") (pintype "passive"))
      (node (ref "U14") (pin "50") (pinfunction "VDD_50") (pintype "passive"))
      (node (ref "U14") (pin "6") (pinfunction "VBAT_6") (pintype "passive"))
      (node (ref "U14") (pin "75") (pinfunction "VDD_75") (pintype "passive"))
      (node (ref "U5") (pin "1") (pinfunction "2_1") (pintype "passive"))
    )
    (net (code "90") (name "VCC5V") (class "Default")
      (node (ref "C25") (pin "1") (pintype "passive"))
      (node (ref "C26") (pin "1") (pintype "passive"))
      (node (ref "C82") (pin "1") (pintype "passive"))
      (node (ref "J1") (pin "1") (pinfunction "0_1") (pintype "passive"))
      (node (ref "JP1") (pin "1") (pinfunction "1_1") (pintype "passive"))
      (node (ref "P1") (pin "1") (pinfunction "1_1") (pintype "passive"))
      (node (ref "P3") (pin "1") (pinfunction "1_1") (pintype "passive"))
      (node (ref "P5") (pin "1") (pinfunction "1_1") (pintype "passive"))
      (node (ref "Q15") (pin "3") (pinfunction "D_3") (pintype "passive"))
      (node (ref "R56") (pin "1") (pinfunction "1_1") (pintype "passive"))
      (node (ref "U9") (pin "1") (pinfunction "2_1") (pintype "passive"))
    )
    (net (code "91") (name "unconnected-(U14A-PA8{slash}MCO1{slash}USART1_CK{slash}TIM1_CH1{slash}I2C3_SCL{slash}OTG_FS_SOF-Pad67)") (class "Default")
      (node (ref "U14") (pin "67") (pinfunction "PA8/MCO1/USART1_CK/TIM1_CH1/I2C3_SCL/OTG_FS_SOF_67") (pintype "passive"))
    )
    (net (code "92") (name "unconnected-(U14A-PB2{slash}BOOT1-Pad37)") (class "Default")
      (node (ref "U14") (pin "37") (pinfunction "PB2/BOOT1_37") (pintype "passive"))
    )
    (net (code "93") (name "unconnected-(U14A-PC3{slash}SPI2_MOSI{slash}I2S2_SD{slash}OTG_HS_ULPI_NXT{slash}ETH_MII_TX_CLK{slash}ADC123_IN13-Pad18)") (class "Default")
      (node (ref "U14") (pin "18") (pinfunction "PC3/SPI2_MOSI/I2S2_SD/OTG_HS_ULPI_NXT/ETH_MII_TX_CLK/ADC123_IN13_18") (pintype "passive"))
    )
    (net (code "94") (name "unconnected-(U14A-PD1{slash}FSMC_D3{slash}CAN1_TX-Pad82)") (class "Default")
      (node (ref "U14") (pin "82") (pinfunction "PD1/FSMC_D3/CAN1_TX_82") (pintype "passive"))
    )
    (net (code "95") (name "unconnected-(U14A-PD2{slash}TIM3_ETR{slash}UART5_RX{slash}SDIO_CMD{slash}DCMI_D11-Pad83)") (class "Default")
      (node (ref "U14") (pin "83") (pinfunction "PD2/TIM3_ETR/UART5_RX/SDIO_CMD/DCMI_D11_83") (pintype "passive"))
    )
    (net (code "96") (name "unconnected-(U14A-PD11{slash}FSMC_CLE{slash}FSMC_A16{slash}USART3_CTS-Pad58)") (class "Default")
      (node (ref "U14") (pin "58") (pinfunction "PD11/FSMC_CLE/FSMC_A16/USART3_CTS_58") (pintype "passive"))
    )
    (net (code "97") (name "unconnected-(U14A-PE2{slash}TRACECLK{slash}FSMC_A23{slash}ETH_MII_TXD3-Pad1)") (class "Default")
      (node (ref "U14") (pin "1") (pinfunction "PE2/TRACECLK/FSMC_A23/ETH_MII_TXD3_1") (pintype "passive"))
    )
    (net (code "98") (name "unconnected-(U14A-PE3{slash}TRACED0{slash}FSMC_A19-Pad2)") (class "Default")
      (node (ref "U14") (pin "2") (pinfunction "PE3/TRACED0/FSMC_A19_2") (pintype "passive"))
    )
    (net (code "99") (name "unconnected-(U14A-PE4{slash}TRACED1{slash}FSMC_A20{slash}DCMI_D4-Pad3)") (class "Default")
      (node (ref "U14") (pin "3") (pinfunction "PE4/TRACED1/FSMC_A20/DCMI_D4_3") (pintype "passive"))
    )
    (net (code "100") (name "unconnected-(U14A-PE7{slash}FSMC_D4{slash}TIM1_ETR-Pad38)") (class "Default")
      (node (ref "U14") (pin "38") (pinfunction "PE7/FSMC_D4/TIM1_ETR_38") (pintype "passive"))
    )
    (net (code "101") (name "unconnected-(U14A-PE15{slash}FSMC_D12{slash}TIM1_BKIN-Pad46)") (class "Default")
      (node (ref "U14") (pin "46") (pinfunction "PE15/FSMC_D12/TIM1_BKIN_46") (pintype "passive"))
    )
  )
)
